# Camera_IR.net
KiCad netlist of a schematic drawn in EasyEDA
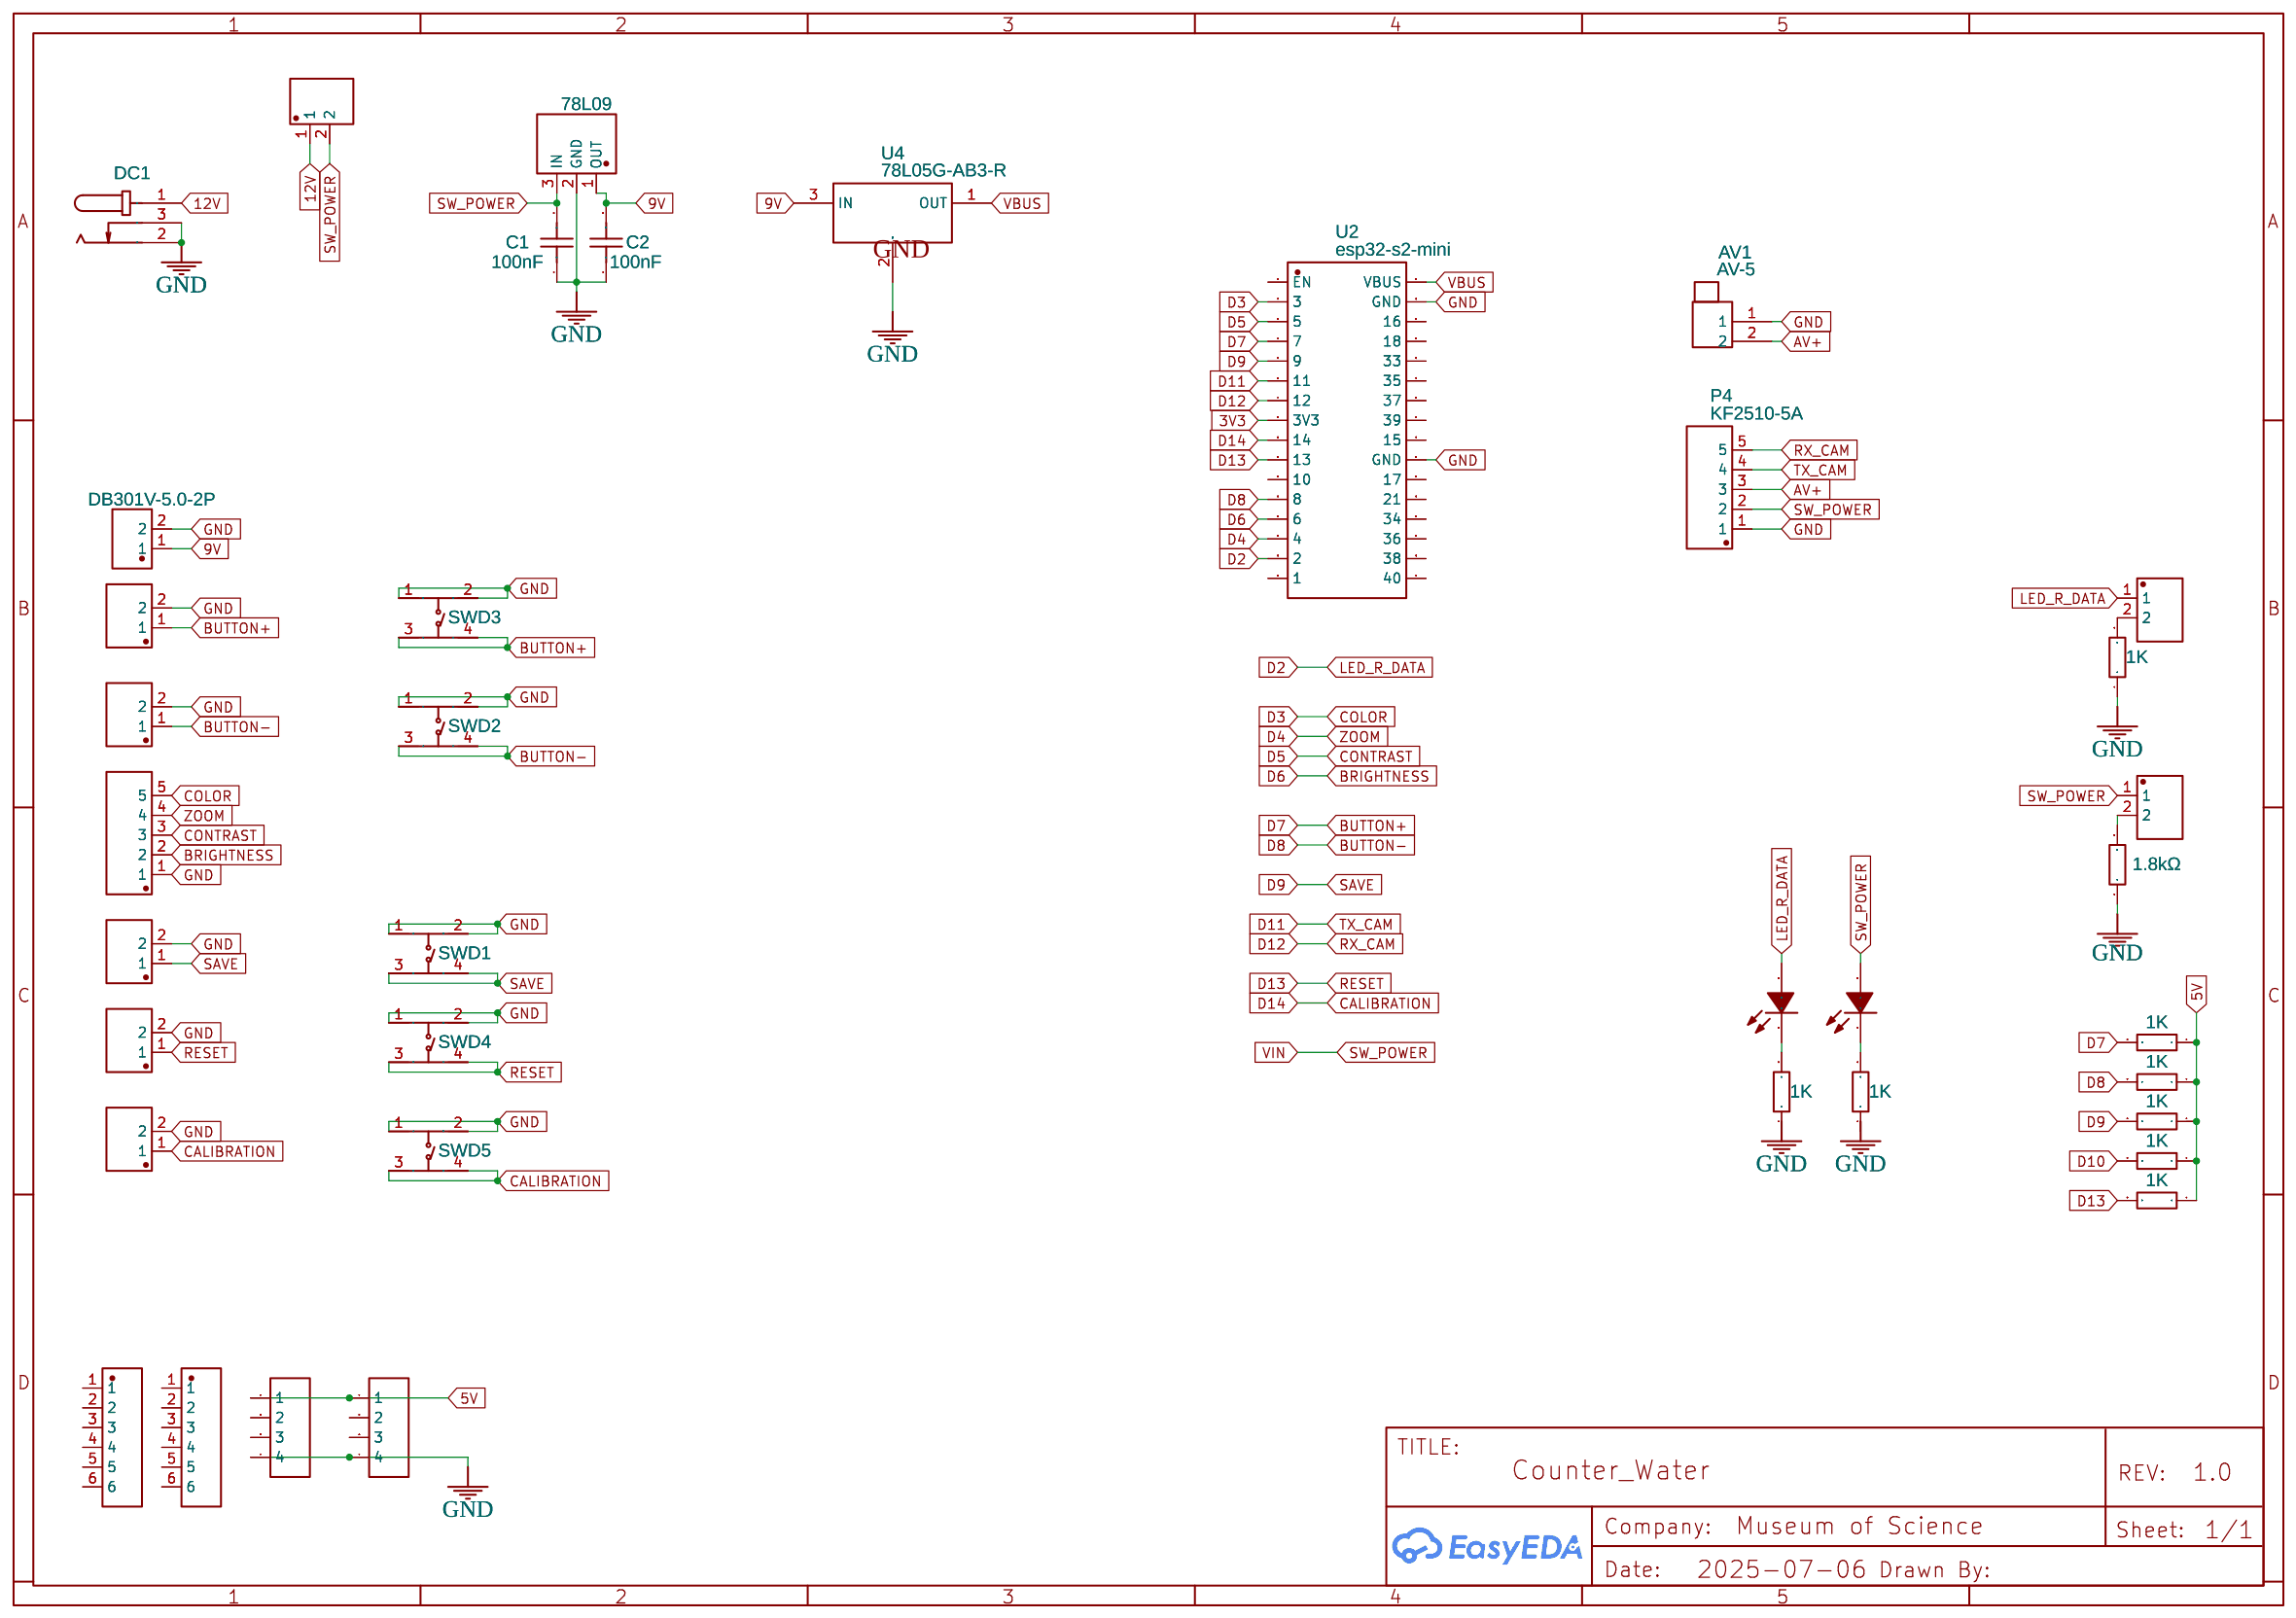
[diagram p0: schematic sheet]

(export (version "E")
  (design (tool "Eeschema 10.0.6"))
  (components
    (comp (ref "AV1")
      (value "AV-5")
      (fields (field (name "Manufacturer") "BOOMELE(博穆精密)"))
      (libsource (lib "") (part "AV-5"))
    )
    (comp (ref "C1")
      (value "100nF")
      (fields
        (field (name "Manufacturer Part") "CC0603KRX7R9BB104")
        (field (name "Manufacturer") "YAGEO(国巨)")
      )
      (libsource (lib "") (part "CC0603KRX7R9BB104"))
    )
    (comp (ref "C2")
      (value "100nF")
      (fields
        (field (name "Manufacturer Part") "CC0603KRX7R9BB104")
        (field (name "Manufacturer") "YAGEO(国巨)")
      )
      (libsource (lib "") (part "CC0603KRX7R9BB104"))
    )
    (comp (ref "D1")
      (value "SAVE")
      (fields (field (name "Manufacturer Part") "KF2510-2A") (field (name "Manufacturer") "BOOMELE"))
      (libsource (lib "") (part "KF2510-2A_2"))
    )
    (comp (ref "D2")
      (value "SAVE")
      (fields (field (name "Manufacturer Part") "KF2510-2A") (field (name "Manufacturer") "BOOMELE"))
      (libsource (lib "") (part "KF2510-2A_2"))
    )
    (comp (ref "D7")
      (value "B+")
      (fields (field (name "Manufacturer Part") "KF2510-2A") (field (name "Manufacturer") "BOOMELE"))
      (libsource (lib "") (part "KF2510-2A"))
    )
    (comp (ref "D8")
      (value "B-")
      (fields (field (name "Manufacturer Part") "KF2510-2A") (field (name "Manufacturer") "BOOMELE"))
      (libsource (lib "") (part "KF2510-2A"))
    )
    (comp (ref "D9")
      (value "SAVE")
      (fields (field (name "Manufacturer Part") "KF2510-2A") (field (name "Manufacturer") "BOOMELE"))
      (libsource (lib "") (part "KF2510-2A"))
    )
    (comp (ref "D13")
      (value "RESET")
      (fields (field (name "Manufacturer Part") "KF2510-2A") (field (name "Manufacturer") "BOOMELE"))
      (libsource (lib "") (part "KF2510-2A"))
    )
    (comp (ref "D14")
      (value "FFC")
      (fields (field (name "Manufacturer Part") "KF2510-2A") (field (name "Manufacturer") "BOOMELE"))
      (libsource (lib "") (part "KF2510-2A"))
    )
    (comp (ref "DC1")
      (value "DC")
      (fields (field (name "Manufacturer Part") "DC005-2.0MM") (field (name "Manufacturer") "SOFNG"))
      (libsource (lib "") (part "DC005-2.0MM"))
    )
    (comp (ref "ERL1")
      (value "1K")
      (fields (field (name "Manufacturer Part") "0603WAF1001T5E") (field (name "Manufacturer") "UniOhm"))
      (libsource (lib "") (part "0603WAF1001T5E"))
    )
    (comp (ref "ERL2")
      (value "1K")
      (fields (field (name "Manufacturer Part") "0603WAF1001T5E") (field (name "Manufacturer") "UniOhm"))
      (libsource (lib "") (part "0603WAF1001T5E_1"))
    )
    (comp (ref "ERL4")
      (value "1K")
      (fields (field (name "Manufacturer Part") "0603WAF1001T5E") (field (name "Manufacturer") "UniOhm"))
      (libsource (lib "") (part "0603WAF1001T5E"))
    )
    (comp (ref "ERL5")
      (value "1K")
      (fields (field (name "Manufacturer Part") "0603WAF1001T5E") (field (name "Manufacturer") "UniOhm"))
      (libsource (lib "") (part "0603WAF1001T5E"))
    )
    (comp (ref "ERL6")
      (value "1K")
      (fields (field (name "Manufacturer Part") "0603WAF1001T5E") (field (name "Manufacturer") "UniOhm"))
      (libsource (lib "") (part "0603WAF1001T5E_1"))
    )
    (comp (ref "ERL9")
      (value "1K")
      (fields (field (name "Manufacturer Part") "0603WAF1001T5E") (field (name "Manufacturer") "UniOhm"))
      (libsource (lib "") (part "0603WAF1001T5E_1"))
    )
    (comp (ref "ERL11")
      (value "1K")
      (fields (field (name "Manufacturer Part") "0603WAF1001T5E") (field (name "Manufacturer") "UniOhm"))
      (libsource (lib "") (part "0603WAF1001T5E_1"))
    )
    (comp (ref "ERL12")
      (value "1K")
      (fields (field (name "Manufacturer Part") "0603WAF1001T5E") (field (name "Manufacturer") "UniOhm"))
      (libsource (lib "") (part "0603WAF1001T5E_1"))
    )
    (comp (ref "J6") (value "HDR-M-2.54_1x4") (libsource (lib "") (part "HDR-M-2.54_1x4")))
    (comp (ref "J7") (value "HDR-M-2.54_1x4") (libsource (lib "") (part "HDR-M-2.54_1x4")))
    (comp (ref "LED4")
      (value "KT-0603R")
      (fields (field (name "Manufacturer") "KENTO"))
      (libsource (lib "") (part "KT-0603R"))
    )
    (comp (ref "LED5")
      (value "KT-0603R")
      (fields (field (name "Manufacturer") "KENTO"))
      (libsource (lib "") (part "KT-0603R"))
    )
    (comp (ref "P1")
      (value "KF2510-5A")
      (fields (field (name "Manufacturer Part") "2510-5A") (field (name "Manufacturer") "BOOMELE(博穆精密)"))
      (libsource (lib "") (part "KF2510-5A"))
    )
    (comp (ref "P2")
      (value "H6")
      (fields (field (name "Manufacturer Part") "2.54-1*6P母") (field (name "Manufacturer") "BOOMELE(博穆精密)"))
      (libsource (lib "") (part "Header-Female-2.54_1x6"))
    )
    (comp (ref "P3")
      (value "H6")
      (fields (field (name "Manufacturer Part") "2.54-1*6P母") (field (name "Manufacturer") "BOOMELE(博穆精密)"))
      (libsource (lib "") (part "Header-Female-2.54_1x6"))
    )
    (comp (ref "P4")
      (value "KF2510-5A")
      (fields (field (name "Manufacturer Part") "2510-5A") (field (name "Manufacturer") "BOOMELE(博穆精密)"))
      (libsource (lib "") (part "KF2510-5A"))
    )
    (comp (ref "R5")
      (value "1.8kΩ")
      (fields
        (field (name "Manufacturer Part") "0603WAF1801T5E")
        (field (name "Manufacturer") "UNI-ROYAL(厚声)")
      )
      (libsource (lib "") (part "0603WAF1801T5E"))
    )
    (comp (ref "SWD1")
      (value "TC-6610-7-160G")
      (fields (field (name "Manufacturer") "HCTL(华灿天禄)"))
      (libsource (lib "") (part "TC-6610-7-160G"))
    )
    (comp (ref "SWD2")
      (value "TC-6610-7-160G")
      (fields (field (name "Manufacturer") "HCTL(华灿天禄)"))
      (libsource (lib "") (part "TC-6610-7-160G"))
    )
    (comp (ref "SWD3")
      (value "TC-6610-7-160G")
      (fields (field (name "Manufacturer") "HCTL(华灿天禄)"))
      (libsource (lib "") (part "TC-6610-7-160G"))
    )
    (comp (ref "SWD4")
      (value "TC-6610-7-160G")
      (fields (field (name "Manufacturer") "HCTL(华灿天禄)"))
      (libsource (lib "") (part "TC-6610-7-160G"))
    )
    (comp (ref "SWD5")
      (value "TC-6610-7-160G")
      (fields (field (name "Manufacturer") "HCTL(华灿天禄)"))
      (libsource (lib "") (part "TC-6610-7-160G"))
    )
    (comp (ref "SW_P")
      (value "SW_P")
      (fields (field (name "Manufacturer Part") "KF2510-2A") (field (name "Manufacturer") "BOOMELE"))
      (libsource (lib "") (part "KF2510-2A_1"))
    )
    (comp (ref "U1")
      (value "78L09")
      (fields (field (name "Manufacturer") "CBI(创基)"))
      (libsource (lib "") (part "78L09U 78L09"))
    )
    (comp (ref "U2") (value "esp32-s2-mini") (libsource (lib "") (part "esp32-s2-mini")))
    (comp (ref "U3")
      (value "DB301V-5.0-2P")
      (fields
        (field (name "Manufacturer Part") "DB301V-5.0-2P-BU-S")
        (field (name "Manufacturer") "DORABO(地博电气)")
      )
      (libsource (lib "") (part "DB301V-5.0-2P"))
    )
    (comp (ref "U4")
      (value "78L05G-AB3-R")
      (fields (field (name "Manufacturer") "UTC(友顺)"))
      (libsource (lib "") (part "78L05G-AB3-R"))
    )
  )
  (nets
    (net (code "1") (name "3V3") (class "Default")
      (node (ref "U2") (pin "8") (pinfunction "3V3_8") (pintype "unspecified"))
    )
    (net (code "2") (name "5V") (class "Default")
      (node (ref "ERL11") (pin "1") (pinfunction "1_1") (pintype "input"))
      (node (ref "ERL12") (pin "1") (pinfunction "1_1") (pintype "input"))
      (node (ref "ERL2") (pin "1") (pinfunction "1_1") (pintype "input"))
      (node (ref "ERL6") (pin "1") (pinfunction "1_1") (pintype "input"))
      (node (ref "ERL9") (pin "1") (pinfunction "1_1") (pintype "input"))
      (node (ref "J6") (pin "1") (pinfunction "1_1") (pintype "unspecified"))
      (node (ref "J7") (pin "1") (pinfunction "1_1") (pintype "unspecified"))
    )
    (net (code "3") (name "9V") (class "Default")
      (node (ref "C2") (pin "2") (pinfunction "2_2") (pintype "unspecified"))
      (node (ref "U1") (pin "1") (pinfunction "OUT_1") (pintype "unspecified"))
      (node (ref "U3") (pin "1") (pinfunction "1_1") (pintype "unspecified"))
      (node (ref "U4") (pin "3") (pinfunction "IN_3") (pintype "passive"))
    )
    (net (code "4") (name "12V") (class "Default")
      (node (ref "DC1") (pin "1") (pinfunction "1_1") (pintype "unspecified"))
      (node (ref "SW_P") (pin "1") (pinfunction "1_1") (pintype "unspecified"))
    )
    (net (code "5") (name "AV+") (class "Default")
      (node (ref "AV1") (pin "2") (pinfunction "2_2") (pintype "unspecified"))
      (node (ref "P4") (pin "3") (pinfunction "3_3") (pintype "unspecified"))
    )
    (net (code "6") (name "BRIGHTNESS") (class "Default")
      (node (ref "P1") (pin "2") (pinfunction "2_2") (pintype "unspecified"))
      (node (ref "U2") (pin "13") (pinfunction "6_13") (pintype "unspecified"))
    )
    (net (code "7") (name "BUTTON+") (class "Default")
      (node (ref "D7") (pin "1") (pinfunction "1_1") (pintype "unspecified"))
      (node (ref "ERL6") (pin "2") (pinfunction "2_2") (pintype "input"))
      (node (ref "SWD3") (pin "3") (pinfunction "3_3") (pintype "unspecified"))
      (node (ref "SWD3") (pin "4") (pinfunction "4_4") (pintype "unspecified"))
      (node (ref "U2") (pin "4") (pinfunction "7_4") (pintype "unspecified"))
    )
    (net (code "8") (name "BUTTON-") (class "Default")
      (node (ref "D8") (pin "1") (pinfunction "1_1") (pintype "unspecified"))
      (node (ref "ERL11") (pin "2") (pinfunction "2_2") (pintype "input"))
      (node (ref "SWD2") (pin "3") (pinfunction "3_3") (pintype "unspecified"))
      (node (ref "SWD2") (pin "4") (pinfunction "4_4") (pintype "unspecified"))
      (node (ref "U2") (pin "12") (pinfunction "8_12") (pintype "unspecified"))
    )
    (net (code "9") (name "CALIBRATION") (class "Default")
      (node (ref "D14") (pin "1") (pinfunction "1_1") (pintype "unspecified"))
      (node (ref "SWD5") (pin "3") (pinfunction "3_3") (pintype "unspecified"))
      (node (ref "SWD5") (pin "4") (pinfunction "4_4") (pintype "unspecified"))
      (node (ref "U2") (pin "9") (pinfunction "14_9") (pintype "unspecified"))
    )
    (net (code "10") (name "COLOR") (class "Default")
      (node (ref "P1") (pin "5") (pinfunction "5_5") (pintype "unspecified"))
      (node (ref "U2") (pin "2") (pinfunction "3_2") (pintype "unspecified"))
    )
    (net (code "11") (name "CONTRAST") (class "Default")
      (node (ref "P1") (pin "3") (pinfunction "3_3") (pintype "unspecified"))
      (node (ref "U2") (pin "3") (pinfunction "5_3") (pintype "unspecified"))
    )
    (net (code "12") (name "D2") (class "Default")
      (node (ref "D2") (pin "1") (pinfunction "1_1") (pintype "unspecified"))
      (node (ref "LED5") (pin "2") (pinfunction "A_2") (pintype "unspecified"))
      (node (ref "U2") (pin "15") (pinfunction "2_15") (pintype "unspecified"))
    )
    (net (code "13") (name "D4") (class "Default")
      (node (ref "P1") (pin "4") (pinfunction "4_4") (pintype "unspecified"))
      (node (ref "U2") (pin "14") (pinfunction "4_14") (pintype "unspecified"))
    )
    (net (code "14") (name "D9") (class "Default")
      (node (ref "D9") (pin "1") (pinfunction "1_1") (pintype "unspecified"))
      (node (ref "ERL9") (pin "2") (pinfunction "2_2") (pintype "input"))
      (node (ref "SWD1") (pin "3") (pinfunction "3_3") (pintype "unspecified"))
      (node (ref "SWD1") (pin "4") (pinfunction "4_4") (pintype "unspecified"))
      (node (ref "U2") (pin "5") (pinfunction "9_5") (pintype "unspecified"))
    )
    (net (code "15") (name "D10") (class "Default")
      (node (ref "ERL12") (pin "2") (pinfunction "2_2") (pintype "input"))
    )
    (net (code "16") (name "D11") (class "Default")
      (node (ref "P4") (pin "4") (pinfunction "4_4") (pintype "unspecified"))
      (node (ref "U2") (pin "6") (pinfunction "11_6") (pintype "unspecified"))
    )
    (net (code "17") (name "D12") (class "Default")
      (node (ref "P4") (pin "5") (pinfunction "5_5") (pintype "unspecified"))
      (node (ref "U2") (pin "7") (pinfunction "12_7") (pintype "unspecified"))
    )
    (net (code "18") (name "D13") (class "Default")
      (node (ref "D13") (pin "1") (pinfunction "1_1") (pintype "unspecified"))
      (node (ref "ERL2") (pin "2") (pinfunction "2_2") (pintype "input"))
      (node (ref "SWD4") (pin "3") (pinfunction "3_3") (pintype "unspecified"))
      (node (ref "SWD4") (pin "4") (pinfunction "4_4") (pintype "unspecified"))
      (node (ref "U2") (pin "10") (pinfunction "13_10") (pintype "unspecified"))
    )
    (net (code "19") (name "GND") (class "Default")
      (node (ref "AV1") (pin "1") (pinfunction "1_1") (pintype "unspecified"))
      (node (ref "C1") (pin "1") (pinfunction "1_1") (pintype "unspecified"))
      (node (ref "C2") (pin "1") (pinfunction "1_1") (pintype "unspecified"))
      (node (ref "D13") (pin "2") (pinfunction "2_2") (pintype "unspecified"))
      (node (ref "D14") (pin "2") (pinfunction "2_2") (pintype "unspecified"))
      (node (ref "D7") (pin "2") (pinfunction "2_2") (pintype "unspecified"))
      (node (ref "D8") (pin "2") (pinfunction "2_2") (pintype "unspecified"))
      (node (ref "D9") (pin "2") (pinfunction "2_2") (pintype "unspecified"))
      (node (ref "DC1") (pin "2") (pinfunction "2_2") (pintype "unspecified"))
      (node (ref "DC1") (pin "3") (pinfunction "3_3") (pintype "unspecified"))
      (node (ref "ERL1") (pin "1") (pinfunction "1_1") (pintype "input"))
      (node (ref "ERL4") (pin "1") (pinfunction "1_1") (pintype "input"))
      (node (ref "ERL5") (pin "1") (pinfunction "1_1") (pintype "input"))
      (node (ref "J6") (pin "4") (pinfunction "4_4") (pintype "unspecified"))
      (node (ref "J7") (pin "4") (pinfunction "4_4") (pintype "unspecified"))
      (node (ref "P1") (pin "1") (pinfunction "1_1") (pintype "unspecified"))
      (node (ref "P4") (pin "1") (pinfunction "1_1") (pintype "unspecified"))
      (node (ref "R5") (pin "1") (pinfunction "1_1") (pintype "input"))
      (node (ref "SWD1") (pin "1") (pinfunction "1_1") (pintype "unspecified"))
      (node (ref "SWD1") (pin "2") (pinfunction "2_2") (pintype "unspecified"))
      (node (ref "SWD2") (pin "1") (pinfunction "1_1") (pintype "unspecified"))
      (node (ref "SWD2") (pin "2") (pinfunction "2_2") (pintype "unspecified"))
      (node (ref "SWD3") (pin "1") (pinfunction "1_1") (pintype "unspecified"))
      (node (ref "SWD3") (pin "2") (pinfunction "2_2") (pintype "unspecified"))
      (node (ref "SWD4") (pin "1") (pinfunction "1_1") (pintype "unspecified"))
      (node (ref "SWD4") (pin "2") (pinfunction "2_2") (pintype "unspecified"))
      (node (ref "SWD5") (pin "1") (pinfunction "1_1") (pintype "unspecified"))
      (node (ref "SWD5") (pin "2") (pinfunction "2_2") (pintype "unspecified"))
      (node (ref "U1") (pin "2") (pinfunction "GND_2") (pintype "unspecified"))
      (node (ref "U2") (pin "23") (pinfunction "GND_23") (pintype "unspecified"))
      (node (ref "U2") (pin "31") (pinfunction "GND_31") (pintype "unspecified"))
      (node (ref "U3") (pin "2") (pinfunction "2_2") (pintype "unspecified"))
      (node (ref "U4") (pin "2") (pinfunction "GND_2") (pintype "passive"))
    )
    (net (code "20") (name "Net-(D1-Pad2)") (class "Default")
      (node (ref "D1") (pin "2") (pinfunction "2_2") (pintype "unspecified"))
      (node (ref "R5") (pin "2") (pinfunction "2_2") (pintype "input"))
    )
    (net (code "21") (name "Net-(D2-Pad2)") (class "Default")
      (node (ref "D2") (pin "2") (pinfunction "2_2") (pintype "unspecified"))
      (node (ref "ERL5") (pin "2") (pinfunction "2_2") (pintype "input"))
    )
    (net (code "22") (name "Net-(LED4-K)") (class "Default")
      (node (ref "ERL4") (pin "2") (pinfunction "2_2") (pintype "input"))
      (node (ref "LED4") (pin "1") (pinfunction "K_1") (pintype "unspecified"))
    )
    (net (code "23") (name "Net-(LED5-K)") (class "Default")
      (node (ref "ERL1") (pin "2") (pinfunction "2_2") (pintype "input"))
      (node (ref "LED5") (pin "1") (pinfunction "K_1") (pintype "unspecified"))
    )
    (net (code "24") (name "SW_POWER") (class "Default")
      (node (ref "C1") (pin "2") (pinfunction "2_2") (pintype "unspecified"))
      (node (ref "D1") (pin "1") (pinfunction "1_1") (pintype "unspecified"))
      (node (ref "LED4") (pin "2") (pinfunction "A_2") (pintype "unspecified"))
      (node (ref "P4") (pin "2") (pinfunction "2_2") (pintype "unspecified"))
      (node (ref "SW_P") (pin "2") (pinfunction "2_2") (pintype "unspecified"))
      (node (ref "U1") (pin "3") (pinfunction "IN_3") (pintype "unspecified"))
    )
    (net (code "25") (name "VBUS") (class "Default")
      (node (ref "U2") (pin "32") (pinfunction "VBUS_32") (pintype "unspecified"))
      (node (ref "U4") (pin "1") (pinfunction "OUT_1") (pintype "passive"))
    )
    (net (code "26") (name "unconnected-(J6-Pad2)") (class "Default")
      (node (ref "J6") (pin "2") (pinfunction "2_2") (pintype "unspecified"))
    )
    (net (code "27") (name "unconnected-(J6-Pad3)") (class "Default")
      (node (ref "J6") (pin "3") (pinfunction "3_3") (pintype "unspecified"))
    )
    (net (code "28") (name "unconnected-(J7-Pad2)") (class "Default")
      (node (ref "J7") (pin "2") (pinfunction "2_2") (pintype "unspecified"))
    )
    (net (code "29") (name "unconnected-(J7-Pad3)") (class "Default")
      (node (ref "J7") (pin "3") (pinfunction "3_3") (pintype "unspecified"))
    )
    (net (code "30") (name "unconnected-(P2-Pad1)") (class "Default")
      (node (ref "P2") (pin "1") (pinfunction "1_1") (pintype "unspecified"))
    )
    (net (code "31") (name "unconnected-(P2-Pad2)") (class "Default")
      (node (ref "P2") (pin "2") (pinfunction "2_2") (pintype "unspecified"))
    )
    (net (code "32") (name "unconnected-(P2-Pad3)") (class "Default")
      (node (ref "P2") (pin "3") (pinfunction "3_3") (pintype "unspecified"))
    )
    (net (code "33") (name "unconnected-(P2-Pad4)") (class "Default")
      (node (ref "P2") (pin "4") (pinfunction "4_4") (pintype "unspecified"))
    )
    (net (code "34") (name "unconnected-(P2-Pad5)") (class "Default")
      (node (ref "P2") (pin "5") (pinfunction "5_5") (pintype "unspecified"))
    )
    (net (code "35") (name "unconnected-(P2-Pad6)") (class "Default")
      (node (ref "P2") (pin "6") (pinfunction "6_6") (pintype "unspecified"))
    )
    (net (code "36") (name "unconnected-(P3-Pad1)") (class "Default")
      (node (ref "P3") (pin "1") (pinfunction "1_1") (pintype "unspecified"))
    )
    (net (code "37") (name "unconnected-(P3-Pad2)") (class "Default")
      (node (ref "P3") (pin "2") (pinfunction "2_2") (pintype "unspecified"))
    )
    (net (code "38") (name "unconnected-(P3-Pad3)") (class "Default")
      (node (ref "P3") (pin "3") (pinfunction "3_3") (pintype "unspecified"))
    )
    (net (code "39") (name "unconnected-(P3-Pad4)") (class "Default")
      (node (ref "P3") (pin "4") (pinfunction "4_4") (pintype "unspecified"))
    )
    (net (code "40") (name "unconnected-(P3-Pad5)") (class "Default")
      (node (ref "P3") (pin "5") (pinfunction "5_5") (pintype "unspecified"))
    )
    (net (code "41") (name "unconnected-(P3-Pad6)") (class "Default")
      (node (ref "P3") (pin "6") (pinfunction "6_6") (pintype "unspecified"))
    )
    (net (code "42") (name "unconnected-(U2-1-Pad16)") (class "Default")
      (node (ref "U2") (pin "16") (pinfunction "1_16") (pintype "unspecified"))
    )
    (net (code "43") (name "unconnected-(U2-10-Pad11)") (class "Default")
      (node (ref "U2") (pin "11") (pinfunction "10_11") (pintype "unspecified"))
    )
    (net (code "44") (name "unconnected-(U2-15-Pad24)") (class "Default")
      (node (ref "U2") (pin "24") (pinfunction "15_24") (pintype "unspecified"))
    )
    (net (code "45") (name "unconnected-(U2-16-Pad30)") (class "Default")
      (node (ref "U2") (pin "30") (pinfunction "16_30") (pintype "unspecified"))
    )
    (net (code "46") (name "unconnected-(U2-17-Pad22)") (class "Default")
      (node (ref "U2") (pin "22") (pinfunction "17_22") (pintype "unspecified"))
    )
    (net (code "47") (name "unconnected-(U2-18-Pad29)") (class "Default")
      (node (ref "U2") (pin "29") (pinfunction "18_29") (pintype "unspecified"))
    )
    (net (code "48") (name "unconnected-(U2-33-Pad28)") (class "Default")
      (node (ref "U2") (pin "28") (pinfunction "33_28") (pintype "unspecified"))
    )
    (net (code "49") (name "unconnected-(U2-34-Pad20)") (class "Default")
      (node (ref "U2") (pin "20") (pinfunction "34_20") (pintype "unspecified"))
    )
    (net (code "50") (name "unconnected-(U2-35-Pad27)") (class "Default")
      (node (ref "U2") (pin "27") (pinfunction "35_27") (pintype "unspecified"))
    )
    (net (code "51") (name "unconnected-(U2-36-Pad19)") (class "Default")
      (node (ref "U2") (pin "19") (pinfunction "36_19") (pintype "unspecified"))
    )
    (net (code "52") (name "unconnected-(U2-37-Pad26)") (class "Default")
      (node (ref "U2") (pin "26") (pinfunction "37_26") (pintype "unspecified"))
    )
    (net (code "53") (name "unconnected-(U2-38-Pad18)") (class "Default")
      (node (ref "U2") (pin "18") (pinfunction "38_18") (pintype "unspecified"))
    )
    (net (code "54") (name "unconnected-(U2-39-Pad25)") (class "Default")
      (node (ref "U2") (pin "25") (pinfunction "39_25") (pintype "unspecified"))
    )
    (net (code "55") (name "unconnected-(U2-40-Pad17)") (class "Default")
      (node (ref "U2") (pin "17") (pinfunction "40_17") (pintype "unspecified"))
    )
    (net (code "56") (name "unconnected-(U2-EN-Pad1)") (class "Default")
      (node (ref "U2") (pin "1") (pinfunction "EN_1") (pintype "unspecified"))
    )
    (net (code "57") (name "unconnected-(U2-Pad21)") (class "Default")
      (node (ref "U2") (pin "21") (pinfunction "21_21") (pintype "unspecified"))
    )
  )
)
